# LPCB235_-_SPI_UART_-_GROUP_B1.net
KiCad netlist of a schematic drawn in Altium Designer
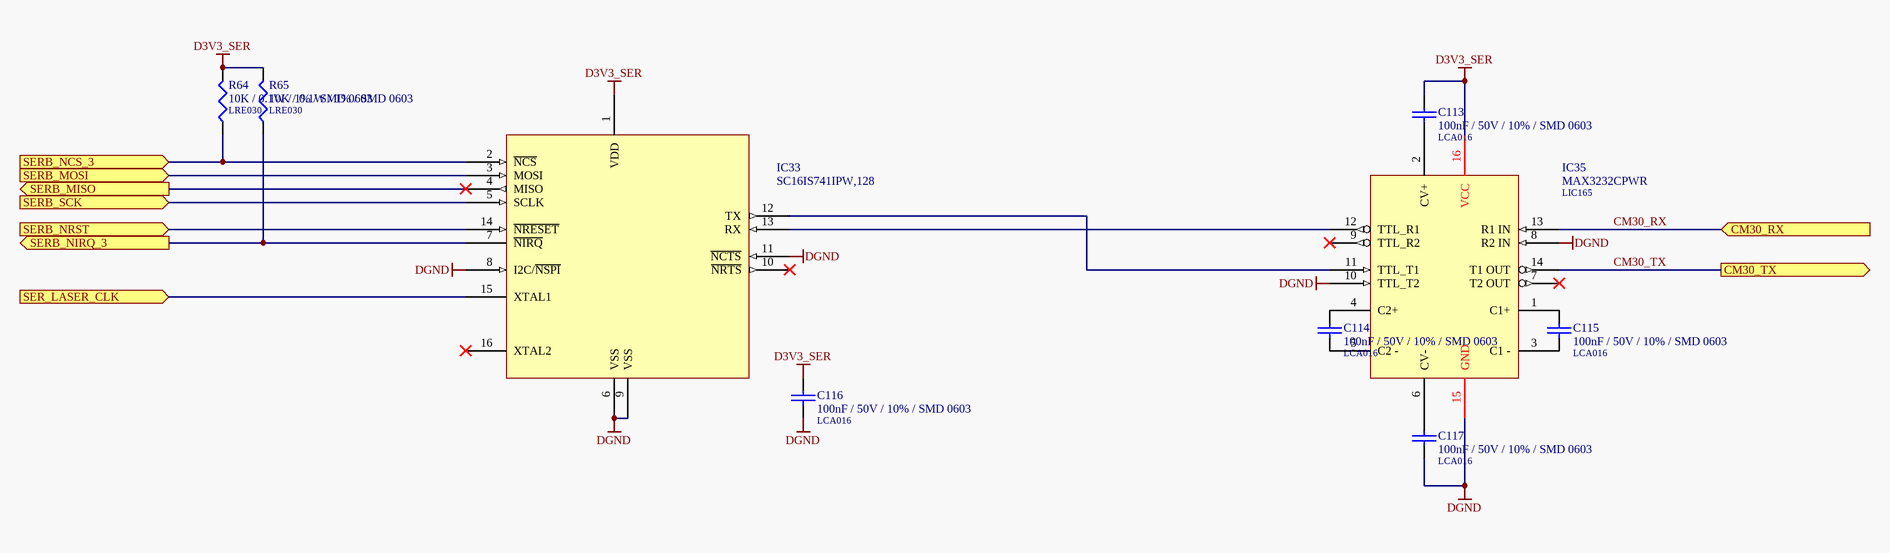
[diagram p0: LPCB235 - SPI UART - GROUP B1.SchDoc]

(export (version "E")
  (design (tool "Eeschema 10.0.6"))
  (components
    (comp (ref "C113")
      (value "100nF / 50V / 10% / SMD 0603")
      (footprint "LFP011__CC1608-0603-IPC7351_B")
      (description "Capacitor, Ceramic Chip, 100nF (0.1uF), 50V, 5%, SMD 0603 [LCA016]")
      (fields (field (name "LDL_NUMBER") "LCA016"))
      (libsource (lib "LDL_Capacitors") (part "100nF / 50V / 10% / SMD 0603"))
    )
    (comp (ref "C114")
      (value "100nF / 50V / 10% / SMD 0603")
      (footprint "LFP011__CC1608-0603-IPC7351_B")
      (description "Capacitor, Ceramic Chip, 100nF (0.1uF), 50V, 5%, SMD 0603 [LCA016]")
      (fields (field (name "LDL_NUMBER") "LCA016"))
      (libsource (lib "LDL_Capacitors") (part "100nF / 50V / 10% / SMD 0603"))
    )
    (comp (ref "C115")
      (value "100nF / 50V / 10% / SMD 0603")
      (footprint "LFP011__CC1608-0603-IPC7351_B")
      (description "Capacitor, Ceramic Chip, 100nF (0.1uF), 50V, 5%, SMD 0603 [LCA016]")
      (fields (field (name "LDL_NUMBER") "LCA016"))
      (libsource (lib "LDL_Capacitors") (part "100nF / 50V / 10% / SMD 0603"))
    )
    (comp (ref "C116")
      (value "100nF / 50V / 10% / SMD 0603")
      (footprint "LFP011__CC1608-0603-IPC7351_B")
      (description "Capacitor, Ceramic Chip, 100nF (0.1uF), 50V, 5%, SMD 0603 [LCA016]")
      (fields (field (name "LDL_NUMBER") "LCA016"))
      (libsource (lib "LDL_Capacitors") (part "100nF / 50V / 10% / SMD 0603"))
    )
    (comp (ref "C117")
      (value "100nF / 50V / 10% / SMD 0603")
      (footprint "LFP011__CC1608-0603-IPC7351_B")
      (description "Capacitor, Ceramic Chip, 100nF (0.1uF), 50V, 5%, SMD 0603 [LCA016]")
      (fields (field (name "LDL_NUMBER") "LCA016"))
      (libsource (lib "LDL_Capacitors") (part "100nF / 50V / 10% / SMD 0603"))
    )
    (comp (ref "IC33")
      (value "SC16IS741IPW,128")
      (footprint "LFP049__TSSOP-16")
      (description "IC, SPI to UART bridge [LIC472]")
      (libsource (lib "LDL_Semiconductors") (part "SC16IS741IPW,128"))
    )
    (comp (ref "IC35")
      (value "MAX3232CPWR")
      (footprint "LFP049__TSSOP-16")
      (description "IC, RS232 Line Driver, 3.3V, SMD TSSOP16 [LIC165]")
      (fields (field (name "LDL_NUMBER") "LIC165"))
      (libsource (lib "LDL_Semiconductors") (part "MAX3232CPWR"))
    )
    (comp (ref "R64")
      (value "10K / 0.1W / 1% / SMD 0603")
      (footprint "LFP020__CR1608-0603-IPC7351_B")
      (description "Resistor, Ceramic Chip, 10K, 0.1W, 1%, SMD 0603 [LRE030]")
      (fields (field (name "LDL_NUMBER") "LRE030"))
      (libsource (lib "LDL_Resistors") (part "10K / 0.1W / 1% / SMD 0603"))
    )
    (comp (ref "R65")
      (value "10K / 0.1W / 1% / SMD 0603")
      (footprint "LFP020__CR1608-0603-IPC7351_B")
      (description "Resistor, Ceramic Chip, 10K, 0.1W, 1%, SMD 0603 [LRE030]")
      (fields (field (name "LDL_NUMBER") "LRE030"))
      (libsource (lib "LDL_Resistors") (part "10K / 0.1W / 1% / SMD 0603"))
    )
  )
  (nets
    (net (code "1") (name "/CM30_RX") (class "Default")
      (node (ref "IC35") (pin "13") (pinfunction "R1_IN_13") (pintype "input"))
    )
    (net (code "2") (name "/CM30_TX") (class "Default")
      (node (ref "IC35") (pin "14") (pinfunction "T1_OUT_14") (pintype "output"))
    )
    (net (code "3") (name "/SERB_MISO") (class "Default")
      (node (ref "IC33") (pin "4") (pinfunction "MISO_4") (pintype "output+no_connect"))
    )
    (net (code "4") (name "/SERB_MOSI") (class "Default")
      (node (ref "IC33") (pin "3") (pinfunction "MOSI_3") (pintype "input"))
    )
    (net (code "5") (name "/SERB_NCS_3") (class "Default")
      (node (ref "IC33") (pin "2") (pinfunction "~{NCS}_2") (pintype "input"))
      (node (ref "R64") (pin "1") (pintype "passive"))
    )
    (net (code "6") (name "/SERB_NIRQ_3") (class "Default")
      (node (ref "IC33") (pin "7") (pinfunction "~{NIRQ}_7") (pintype "passive"))
      (node (ref "R65") (pin "1") (pintype "passive"))
    )
    (net (code "7") (name "/SERB_NRST") (class "Default")
      (node (ref "IC33") (pin "14") (pinfunction "~{NRESET}_14") (pintype "input"))
    )
    (net (code "8") (name "/SERB_SCK") (class "Default")
      (node (ref "IC33") (pin "5") (pinfunction "SCLK_5") (pintype "input"))
    )
    (net (code "9") (name "/SER_LASER_CLK") (class "Default")
      (node (ref "IC33") (pin "15") (pinfunction "XTAL1_15") (pintype "passive"))
    )
    (net (code "10") (name "D3V3_SER") (class "Default")
      (node (ref "C113") (pin "1") (pintype "passive"))
      (node (ref "C116") (pin "1") (pintype "passive"))
      (node (ref "IC33") (pin "1") (pinfunction "VDD_1") (pintype "power_in"))
      (node (ref "IC35") (pin "16") (pinfunction "VCC_16") (pintype "power_in"))
      (node (ref "R64") (pin "2") (pintype "passive"))
      (node (ref "R65") (pin "2") (pintype "passive"))
    )
    (net (code "11") (name "DGND") (class "Default")
      (node (ref "C116") (pin "2") (pintype "passive"))
      (node (ref "C117") (pin "2") (pintype "passive"))
      (node (ref "IC33") (pin "11") (pinfunction "~{NCTS}_11") (pintype "input"))
      (node (ref "IC33") (pin "6") (pinfunction "VSS_6") (pintype "power_in"))
      (node (ref "IC33") (pin "8") (pinfunction "I2C/~{NSPI}_8") (pintype "input"))
      (node (ref "IC33") (pin "9") (pinfunction "VSS_9") (pintype "power_in"))
      (node (ref "IC35") (pin "10") (pinfunction "TTL_T2_10") (pintype "input"))
      (node (ref "IC35") (pin "15") (pinfunction "GND_15") (pintype "power_in"))
      (node (ref "IC35") (pin "8") (pinfunction "R2_IN_8") (pintype "input"))
    )
    (net (code "12") (name "Net-(IC33-RX)") (class "Default")
      (node (ref "IC33") (pin "13") (pinfunction "RX_13") (pintype "input"))
      (node (ref "IC35") (pin "12") (pinfunction "TTL_R1_12") (pintype "output"))
    )
    (net (code "13") (name "Net-(IC33-TX)") (class "Default")
      (node (ref "IC33") (pin "12") (pinfunction "TX_12") (pintype "output"))
      (node (ref "IC35") (pin "11") (pinfunction "TTL_T1_11") (pintype "input"))
    )
    (net (code "14") (name "Net-(IC35-C1+)") (class "Default")
      (node (ref "C115") (pin "1") (pintype "passive"))
      (node (ref "IC35") (pin "1") (pinfunction "C1+_1") (pintype "passive"))
    )
    (net (code "15") (name "Net-(IC35-C1_-)") (class "Default")
      (node (ref "C115") (pin "2") (pintype "passive"))
      (node (ref "IC35") (pin "3") (pinfunction "C1_-_3") (pintype "passive"))
    )
    (net (code "16") (name "Net-(IC35-C2+)") (class "Default")
      (node (ref "C114") (pin "1") (pintype "passive"))
      (node (ref "IC35") (pin "4") (pinfunction "C2+_4") (pintype "passive"))
    )
    (net (code "17") (name "Net-(IC35-C2_-)") (class "Default")
      (node (ref "C114") (pin "2") (pintype "passive"))
      (node (ref "IC35") (pin "5") (pinfunction "C2_-_5") (pintype "passive"))
    )
    (net (code "18") (name "Net-(IC35-CV+)") (class "Default")
      (node (ref "C113") (pin "2") (pintype "passive"))
      (node (ref "IC35") (pin "2") (pinfunction "CV+_2") (pintype "passive"))
    )
    (net (code "19") (name "Net-(IC35-CV-)") (class "Default")
      (node (ref "C117") (pin "1") (pintype "passive"))
      (node (ref "IC35") (pin "6") (pinfunction "CV-_6") (pintype "passive"))
    )
    (net (code "20") (name "unconnected-(IC33-XTAL2-Pad16)") (class "Default")
      (node (ref "IC33") (pin "16") (pinfunction "XTAL2_16") (pintype "passive+no_connect"))
    )
    (net (code "21") (name "unconnected-(IC33-~{NRTS}-Pad10)") (class "Default")
      (node (ref "IC33") (pin "10") (pinfunction "~{NRTS}_10") (pintype "output+no_connect"))
    )
    (net (code "22") (name "unconnected-(IC35-T2_OUT-Pad7)") (class "Default")
      (node (ref "IC35") (pin "7") (pinfunction "T2_OUT_7") (pintype "output+no_connect"))
    )
    (net (code "23") (name "unconnected-(IC35-TTL_R2-Pad9)") (class "Default")
      (node (ref "IC35") (pin "9") (pinfunction "TTL_R2_9") (pintype "output+no_connect"))
    )
  )
)
